# SCH_Hacker-Card_2024-08-08.net
KiCad netlist of a schematic drawn in EasyEDA
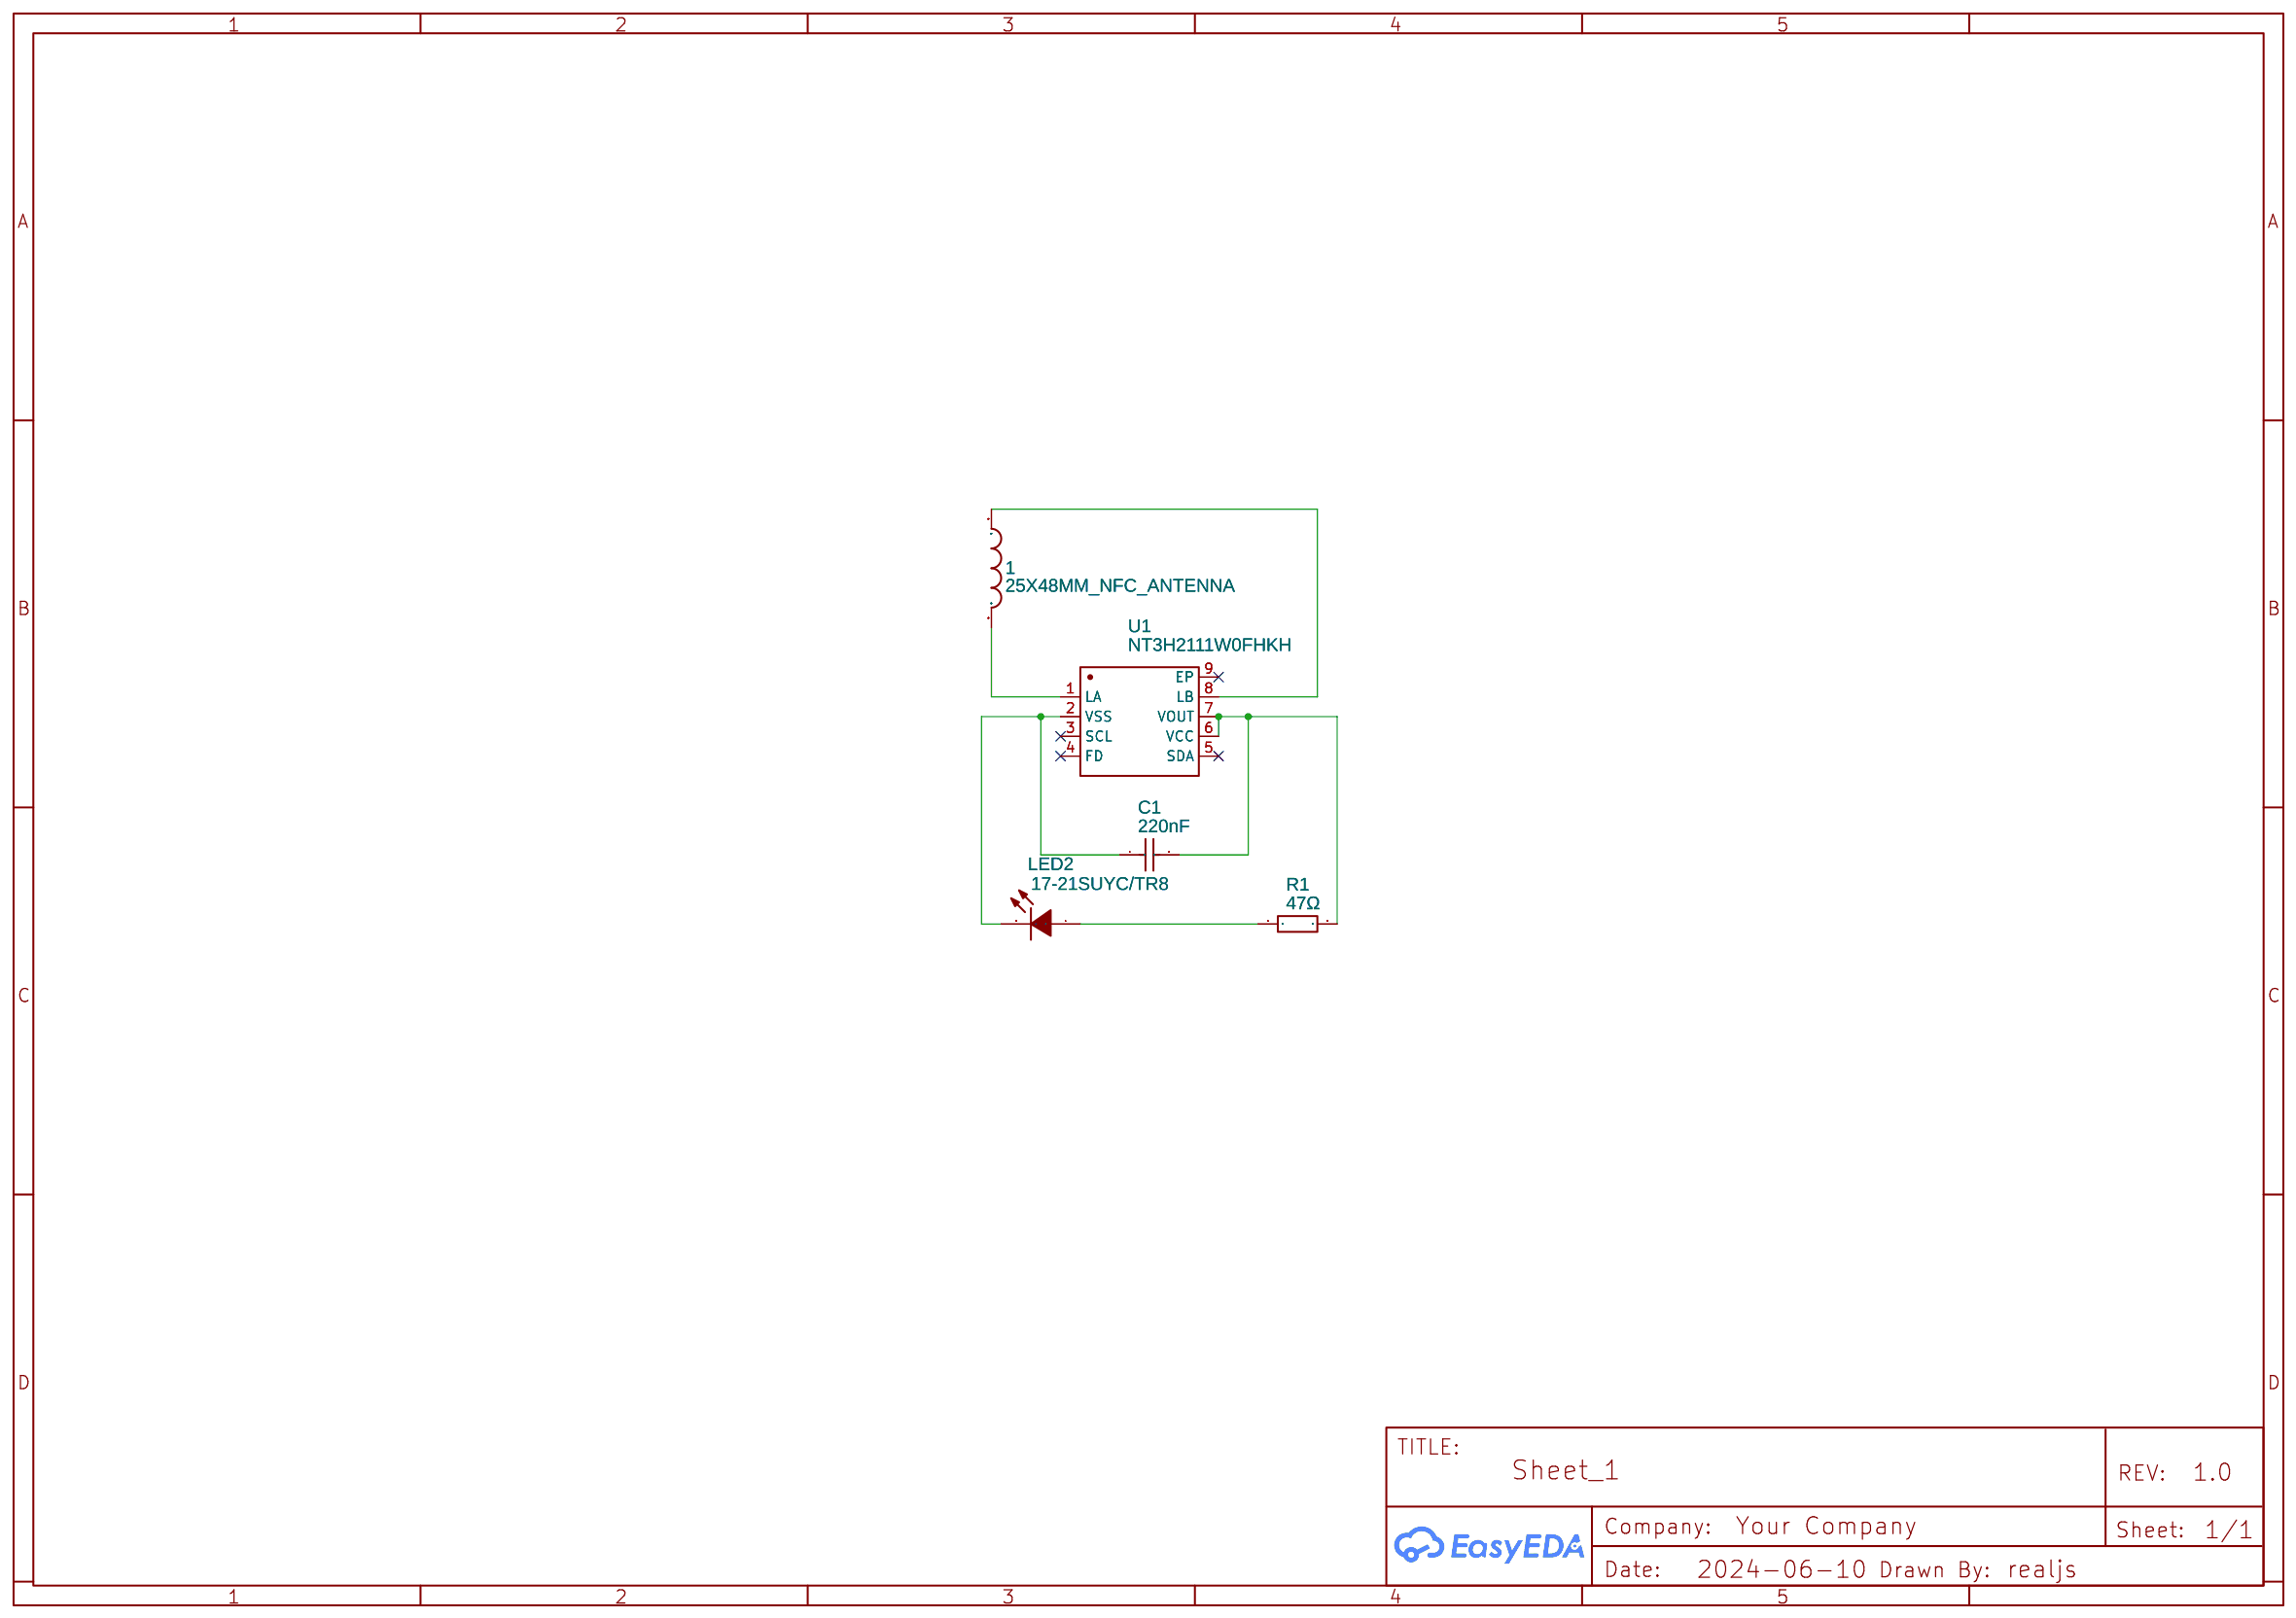
[diagram p0: schematic sheet]

(export (version "E")
  (design (tool "Eeschema 10.0.6"))
  (components
    (comp (ref "1") (value "25X48MM_NFC_ANTENNA") (libsource (lib "") (part "25X48MM_NFC_ANTENNA")))
    (comp (ref "C1")
      (value "220nF")
      (fields
        (field (name "Manufacturer Part") "CL10B224KA8NNNC")
        (field (name "Manufacturer") "SAMSUNG(三星)")
      )
      (libsource (lib "") (part "CL10B224KA8NNNC"))
    )
    (comp (ref "LED2")
      (value "17-21SUYC/TR8")
      (fields (field (name "Manufacturer Part") "KT-0805黄灯") (field (name "Manufacturer") "KENTO"))
      (libsource (lib "") (part "17-21SUYC/TR8"))
    )
    (comp (ref "R1")
      (value "47Ω")
      (fields
        (field (name "Manufacturer Part") "0603WAF470JT5E")
        (field (name "Manufacturer") "UNI-ROYAL(厚声)")
      )
      (libsource (lib "") (part "0603WAF470JT5E"))
    )
    (comp (ref "U1")
      (value "NT3H2111W0FHKH")
      (fields (field (name "Manufacturer") "NXP(恩智浦)"))
      (libsource (lib "") (part "NT3H2111W0FHKH"))
    )
  )
  (nets
    (net (code "1") (name "Net-(LED2-+)") (class "Default")
      (node (ref "LED2") (pin "1") (pinfunction "+_1") (pintype "unspecified"))
      (node (ref "R1") (pin "1") (pinfunction "1_1") (pintype "input"))
    )
    (net (code "2") (name "Net-(LED2--)") (class "Default")
      (node (ref "C1") (pin "1") (pinfunction "1_1") (pintype "input"))
      (node (ref "LED2") (pin "2") (pinfunction "-_2") (pintype "unspecified"))
      (node (ref "U1") (pin "2") (pinfunction "VSS_2") (pintype "unspecified"))
    )
    (net (code "3") (name "Net-(U1-LA)") (class "Default")
      (node (ref "1") (pin "P$2") (pinfunction "P$2_P$2") (pintype "bidirectional"))
      (node (ref "U1") (pin "1") (pinfunction "LA_1") (pintype "unspecified"))
    )
    (net (code "4") (name "Net-(U1-LB)") (class "Default")
      (node (ref "1") (pin "P$1") (pinfunction "P$1_P$1") (pintype "bidirectional"))
      (node (ref "U1") (pin "8") (pinfunction "LB_8") (pintype "unspecified"))
    )
    (net (code "5") (name "Net-(U1-VCC)") (class "Default")
      (node (ref "C1") (pin "2") (pinfunction "2_2") (pintype "input"))
      (node (ref "R1") (pin "2") (pinfunction "2_2") (pintype "input"))
      (node (ref "U1") (pin "6") (pinfunction "VCC_6") (pintype "unspecified"))
      (node (ref "U1") (pin "7") (pinfunction "VOUT_7") (pintype "unspecified"))
    )
    (net (code "6") (name "unconnected-(U1-EP-Pad9)") (class "Default")
      (node (ref "U1") (pin "9") (pinfunction "EP_9") (pintype "unspecified+no_connect"))
    )
    (net (code "7") (name "unconnected-(U1-FD-Pad4)") (class "Default")
      (node (ref "U1") (pin "4") (pinfunction "FD_4") (pintype "unspecified+no_connect"))
    )
    (net (code "8") (name "unconnected-(U1-SCL-Pad3)") (class "Default")
      (node (ref "U1") (pin "3") (pinfunction "SCL_3") (pintype "unspecified+no_connect"))
    )
    (net (code "9") (name "unconnected-(U1-SDA-Pad5)") (class "Default")
      (node (ref "U1") (pin "5") (pinfunction "SDA_5") (pintype "unspecified+no_connect"))
    )
  )
)
